# sensorNodev1_0.net
KiCad netlist of a schematic drawn in EAGLE
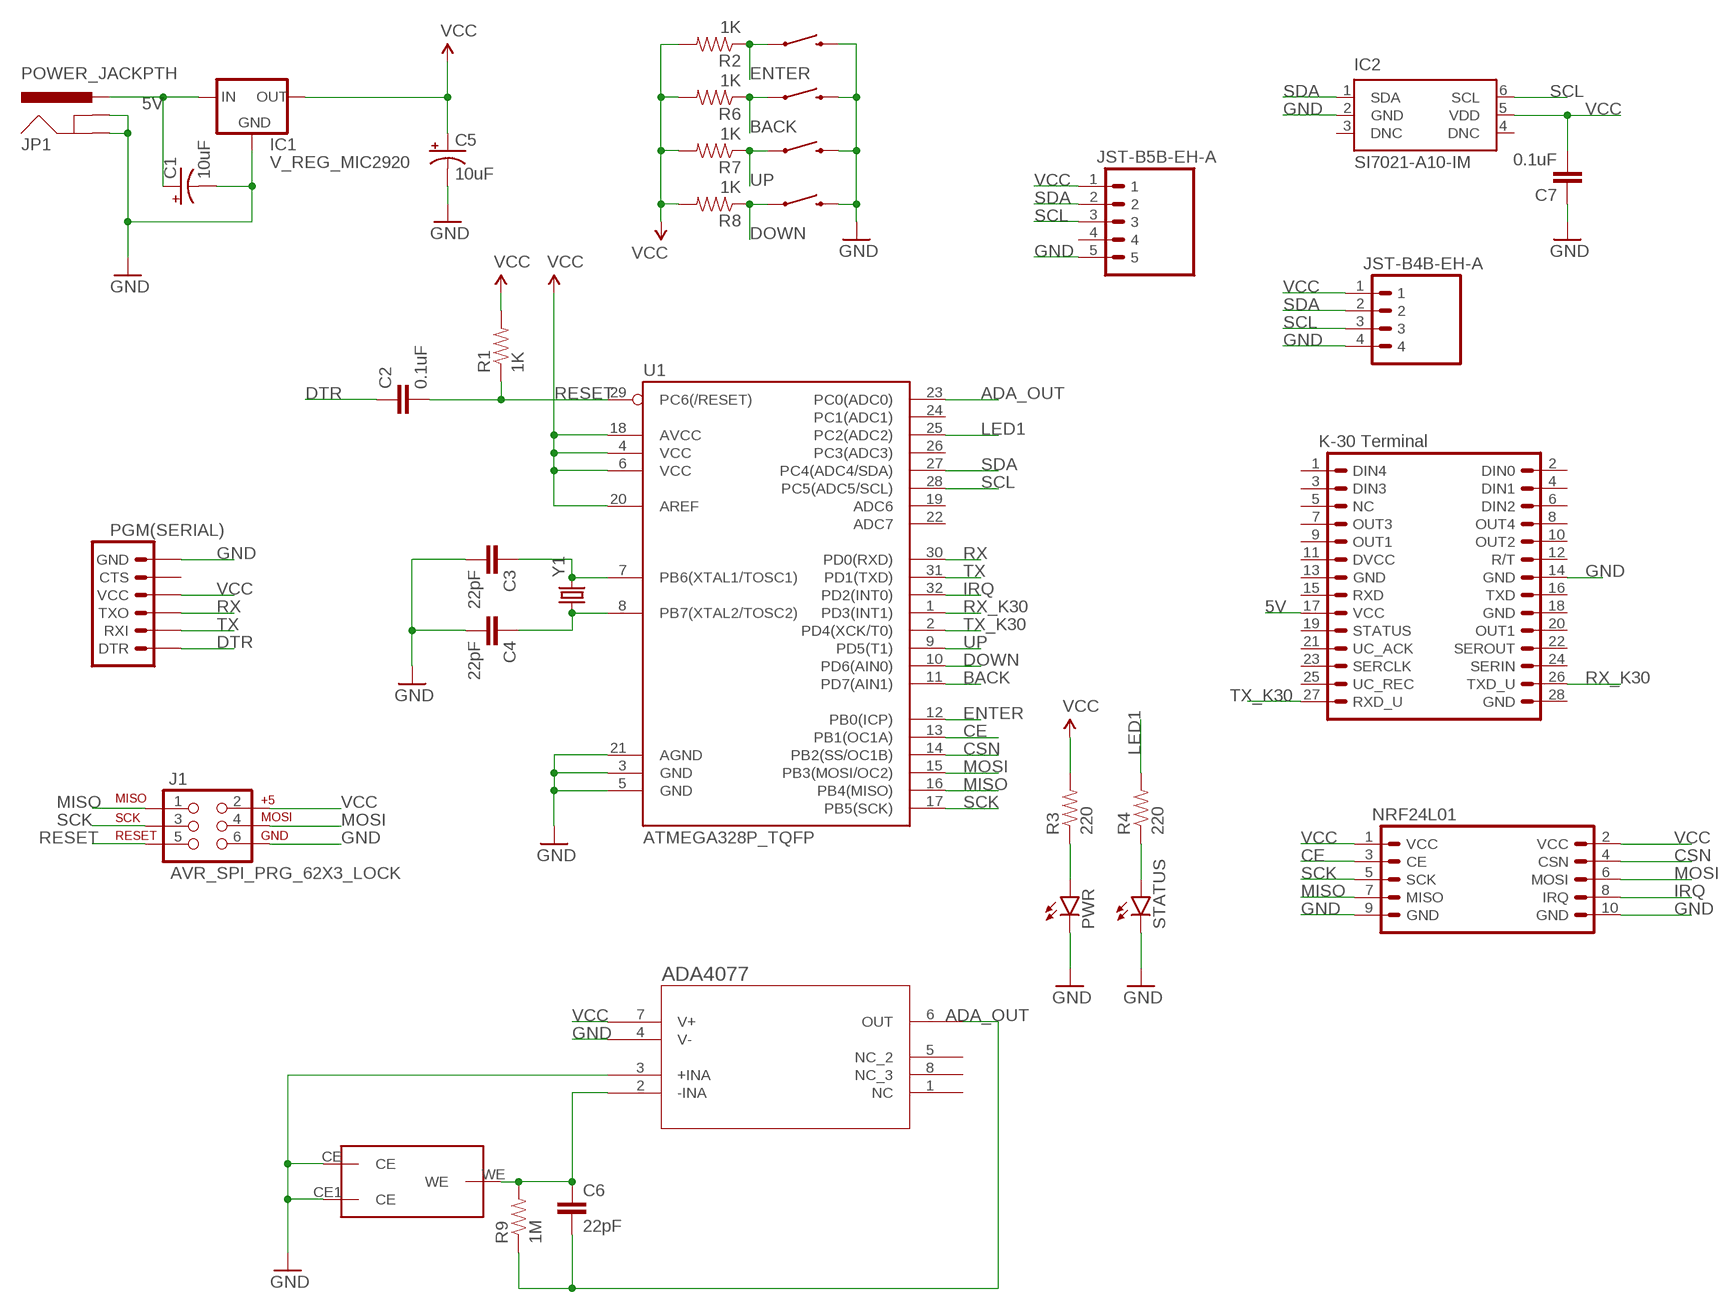
[diagram p0: schematic, sheet 1]

(export (version "E")
  (design (tool "Eeschema 10.0.6"))
  (components
    (comp (ref "BACK")
      (value "SWITCH-MOMENTARY-2SIDE_EZ")
      (footprint "eagle-import:TACTILE-PTH-SIDEEZ")
      (libsource (lib "eagle-import") (part "SWITCH-MOMENTARY-2SIDE_EZ"))
    )
    (comp (ref "C1")
      (value "10uF")
      (footprint "eagle-import:CPOL-RADIAL-10UF-25V")
      (libsource (lib "eagle-import") (part "CAP_POLPTH2"))
    )
    (comp (ref "C2")
      (value "0.1uF")
      (footprint "eagle-import:0603-CAP")
      (libsource (lib "eagle-import") (part "0.1UF-25V(+80/-20%)(0603)"))
    )
    (comp (ref "C3")
      (value "22pF")
      (footprint "eagle-import:0603-CAP")
      (libsource (lib "eagle-import") (part "22PF-50V-5%(0603)"))
    )
    (comp (ref "C4")
      (value "22pF")
      (footprint "eagle-import:0603-CAP")
      (libsource (lib "eagle-import") (part "22PF-50V-5%(0603)"))
    )
    (comp (ref "C5")
      (value "10uF")
      (footprint "eagle-import:CPOL-RADIAL-10UF-25V")
      (libsource (lib "eagle-import") (part "CAP_POLPTH2"))
    )
    (comp (ref "C6")
      (value "22pF")
      (footprint "eagle-import:0603-CAP")
      (libsource (lib "eagle-import") (part "22PF-50V-5%(0603)"))
    )
    (comp (ref "C7")
      (value "0.1uF")
      (footprint "eagle-import:0603-CAP")
      (libsource (lib "eagle-import") (part "0.1UF-25V(+80/-20%)(0603)"))
    )
    (comp (ref "CO2")
      (value "K-30K-30")
      (footprint "eagle-import:K-30")
      (libsource (lib "eagle-import") (part "K-30K-30"))
    )
    (comp (ref "DOWN")
      (value "SWITCH-MOMENTARY-2SIDE_EZ")
      (footprint "eagle-import:TACTILE-PTH-SIDEEZ")
      (libsource (lib "eagle-import") (part "SWITCH-MOMENTARY-2SIDE_EZ"))
    )
    (comp (ref "ENTER")
      (value "SWITCH-MOMENTARY-2SIDE_EZ")
      (footprint "eagle-import:TACTILE-PTH-SIDEEZ")
      (libsource (lib "eagle-import") (part "SWITCH-MOMENTARY-2SIDE_EZ"))
    )
    (comp (ref "IC1")
      (value "V_REG_MIC2920")
      (footprint "eagle-import:SOT223")
      (libsource (lib "eagle-import") (part "V_REG_MIC2920"))
    )
    (comp (ref "IC2")
      (value "SI7021-A10-IM")
      (footprint "eagle-import:DFN6-3X3")
      (fields (field (name "MF") "Silicon Labs") (field (name "MPN") "Si7021-A10-IM"))
      (libsource (lib "eagle-import") (part "SI7021-A10-IM"))
    )
    (comp (ref "J1")
      (value "AVR_SPI_PRG_62X3_LOCK")
      (footprint "eagle-import:2X3_LOCK")
      (libsource (lib "eagle-import") (part "AVR_SPI_PRG_62X3_LOCK"))
    )
    (comp (ref "JP1")
      (value "POWER_JACKPTH")
      (footprint "eagle-import:POWER_JACK_PTH")
      (libsource (lib "eagle-import") (part "POWER_JACKPTH"))
    )
    (comp (ref "LIGHT")
      (value "JST-B4B-EH-A")
      (footprint "eagle-import:JST-B4B-ED-A")
      (libsource (lib "eagle-import") (part "JST-B4B-EH-A"))
    )
    (comp (ref "PGM(SERIAL)")
      (value "ARDUINO_SERIAL_PROGRAMPTH")
      (footprint "eagle-import:1X06")
      (libsource (lib "eagle-import") (part "ARDUINO_SERIAL_PROGRAMPTH"))
    )
    (comp (ref "PWR")
      (value "LED0603")
      (footprint "eagle-import:LED-0603")
      (libsource (lib "eagle-import") (part "LED0603"))
    )
    (comp (ref "R1")
      (value "1K")
      (footprint "eagle-import:0603-RES")
      (libsource (lib "eagle-import") (part "1KOHM-1/10W-1%(0603)"))
    )
    (comp (ref "R2")
      (value "1K")
      (footprint "eagle-import:0603-RES")
      (libsource (lib "eagle-import") (part "1KOHM-1/10W-1%(0603)"))
    )
    (comp (ref "R3")
      (value "220")
      (footprint "eagle-import:0603-RES")
      (libsource (lib "eagle-import") (part "1KOHM-1/10W-1%(0603)"))
    )
    (comp (ref "R4")
      (value "220")
      (footprint "eagle-import:0603-RES")
      (libsource (lib "eagle-import") (part "1KOHM-1/10W-1%(0603)"))
    )
    (comp (ref "R6")
      (value "1K")
      (footprint "eagle-import:0603-RES")
      (libsource (lib "eagle-import") (part "1KOHM-1/10W-1%(0603)"))
    )
    (comp (ref "R7")
      (value "1K")
      (footprint "eagle-import:0603-RES")
      (libsource (lib "eagle-import") (part "1KOHM-1/10W-1%(0603)"))
    )
    (comp (ref "R8")
      (value "1K")
      (footprint "eagle-import:0603-RES")
      (libsource (lib "eagle-import") (part "1KOHM-1/10W-1%(0603)"))
    )
    (comp (ref "R9")
      (value "1M")
      (footprint "eagle-import:0603-RES")
      (libsource (lib "eagle-import") (part "1KOHM-1/10W-1%(0603)"))
    )
    (comp (ref "SCREEN")
      (value "JST-B5B-EH-A")
      (footprint "eagle-import:JST-B5B-ED-A")
      (libsource (lib "eagle-import") (part "JST-B5B-EH-A"))
    )
    (comp (ref "STATUS")
      (value "LED0603")
      (footprint "eagle-import:LED-0603")
      (libsource (lib "eagle-import") (part "LED0603"))
    )
    (comp (ref "U$1")
      (value "TGS5042A")
      (footprint "eagle-import:TGS5042")
      (libsource (lib "eagle-import") (part "TGS5042A"))
    )
    (comp (ref "U$2")
      (value "NRF24L01")
      (footprint "eagle-import:NRF24L01")
      (libsource (lib "eagle-import") (part "NRF24L01"))
    )
    (comp (ref "U1")
      (value "ATMEGA328P_TQFP")
      (footprint "eagle-import:TQFP32-08")
      (libsource (lib "eagle-import") (part "ATMEGA328P_TQFP"))
    )
    (comp (ref "U2")
      (value "ADA4077-1ARZ")
      (footprint "eagle-import:R_8")
      (libsource (lib "eagle-import") (part "ADA4077-1ARZ"))
    )
    (comp (ref "UP")
      (value "SWITCH-MOMENTARY-2SIDE_EZ")
      (footprint "eagle-import:TACTILE-PTH-SIDEEZ")
      (libsource (lib "eagle-import") (part "SWITCH-MOMENTARY-2SIDE_EZ"))
    )
    (comp (ref "Y1")
      (value "CRYSTALHC49US")
      (footprint "eagle-import:HC49US")
      (libsource (lib "eagle-import") (part "CRYSTALHC49US"))
    )
  )
  (nets
    (net (code "1") (name "/5V") (class "Default")
      (node (ref "C1") (pin "1") (pinfunction "+_1") (pintype "passive"))
      (node (ref "CO2") (pin "17") (pinfunction "VCC_17") (pintype "bidirectional"))
      (node (ref "IC1") (pin "1") (pinfunction "IN_1") (pintype "input"))
      (node (ref "JP1") (pin "PWR") (pinfunction "PWR_PWR") (pintype "bidirectional"))
    )
    (net (code "2") (name "/ADA_OUT") (class "Default")
      (node (ref "C6") (pin "2") (pinfunction "2_2") (pintype "passive"))
      (node (ref "R9") (pin "1") (pinfunction "1_1") (pintype "passive"))
      (node (ref "U1") (pin "23") (pinfunction "PC0(ADC0)_23") (pintype "bidirectional"))
      (node (ref "U2") (pin "6") (pinfunction "OUT_6") (pintype "passive"))
    )
    (net (code "3") (name "/BACK") (class "Default")
      (node (ref "BACK") (pin "1") (pinfunction "1_1") (pintype "passive"))
      (node (ref "R6") (pin "1") (pinfunction "1_1") (pintype "passive"))
      (node (ref "U1") (pin "11") (pinfunction "PD7(AIN1)_11") (pintype "bidirectional"))
    )
    (net (code "4") (name "/CE") (class "Default")
      (node (ref "U$2") (pin "3") (pinfunction "CE_3") (pintype "bidirectional"))
      (node (ref "U1") (pin "13") (pinfunction "PB1(OC1A)_13") (pintype "bidirectional"))
    )
    (net (code "5") (name "/CSN") (class "Default")
      (node (ref "U$2") (pin "4") (pinfunction "CSN_4") (pintype "bidirectional"))
      (node (ref "U1") (pin "14") (pinfunction "PB2(SS/OC1B)_14") (pintype "bidirectional"))
    )
    (net (code "6") (name "/DOWN") (class "Default")
      (node (ref "DOWN") (pin "1") (pinfunction "1_1") (pintype "passive"))
      (node (ref "R8") (pin "1") (pinfunction "1_1") (pintype "passive"))
      (node (ref "U1") (pin "10") (pinfunction "PD6(AIN0)_10") (pintype "bidirectional"))
    )
    (net (code "7") (name "/DTR") (class "Default")
      (node (ref "C2") (pin "1") (pinfunction "1_1") (pintype "passive"))
      (node (ref "PGM(SERIAL)") (pin "1") (pinfunction "DTR_1") (pintype "passive"))
    )
    (net (code "8") (name "/ENTER") (class "Default")
      (node (ref "ENTER") (pin "1") (pinfunction "1_1") (pintype "passive"))
      (node (ref "R2") (pin "1") (pinfunction "1_1") (pintype "passive"))
      (node (ref "U1") (pin "12") (pinfunction "PB0(ICP)_12") (pintype "bidirectional"))
    )
    (net (code "9") (name "/IRQ") (class "Default")
      (node (ref "U$2") (pin "8") (pinfunction "IRQ_8") (pintype "bidirectional"))
      (node (ref "U1") (pin "32") (pinfunction "PD2(INT0)_32") (pintype "bidirectional"))
    )
    (net (code "10") (name "/LED1") (class "Default")
      (node (ref "R4") (pin "2") (pinfunction "2_2") (pintype "passive"))
      (node (ref "U1") (pin "25") (pinfunction "PC2(ADC2)_25") (pintype "bidirectional"))
    )
    (net (code "11") (name "/MISO") (class "Default")
      (node (ref "J1") (pin "1") (pinfunction "1_1") (pintype "passive"))
      (node (ref "U$2") (pin "7") (pinfunction "MISO_7") (pintype "bidirectional"))
      (node (ref "U1") (pin "16") (pinfunction "PB4(MISO)_16") (pintype "bidirectional"))
    )
    (net (code "12") (name "/MOSI") (class "Default")
      (node (ref "J1") (pin "4") (pinfunction "4_4") (pintype "passive"))
      (node (ref "U$2") (pin "6") (pinfunction "MOSI_6") (pintype "bidirectional"))
      (node (ref "U1") (pin "15") (pinfunction "PB3(MOSI/OC2)_15") (pintype "bidirectional"))
    )
    (net (code "13") (name "/RESET") (class "Default")
      (node (ref "C2") (pin "2") (pinfunction "2_2") (pintype "passive"))
      (node (ref "J1") (pin "5") (pinfunction "5_5") (pintype "passive"))
      (node (ref "R1") (pin "1") (pinfunction "1_1") (pintype "passive"))
      (node (ref "U1") (pin "29") (pinfunction "PC6(/RESET)_29") (pintype "bidirectional"))
    )
    (net (code "14") (name "/RX") (class "Default")
      (node (ref "PGM(SERIAL)") (pin "3") (pinfunction "TXO_3") (pintype "passive"))
      (node (ref "U1") (pin "30") (pinfunction "PD0(RXD)_30") (pintype "bidirectional"))
    )
    (net (code "15") (name "/RX_K30") (class "Default")
      (node (ref "CO2") (pin "26") (pinfunction "TXD_U_26") (pintype "bidirectional"))
      (node (ref "U1") (pin "1") (pinfunction "PD3(INT1)_1") (pintype "bidirectional"))
    )
    (net (code "16") (name "/SCK") (class "Default")
      (node (ref "J1") (pin "3") (pinfunction "3_3") (pintype "passive"))
      (node (ref "U$2") (pin "5") (pinfunction "SCK_5") (pintype "bidirectional"))
      (node (ref "U1") (pin "17") (pinfunction "PB5(SCK)_17") (pintype "bidirectional"))
    )
    (net (code "17") (name "/SCL") (class "Default")
      (node (ref "IC2") (pin "6") (pinfunction "SCL_6") (pintype "input"))
      (node (ref "LIGHT") (pin "3") (pinfunction "3_3") (pintype "bidirectional"))
      (node (ref "SCREEN") (pin "3") (pinfunction "3_3") (pintype "bidirectional"))
      (node (ref "U1") (pin "28") (pinfunction "PC5(ADC5/SCL)_28") (pintype "bidirectional"))
    )
    (net (code "18") (name "/SDA") (class "Default")
      (node (ref "IC2") (pin "1") (pinfunction "SDA_1") (pintype "bidirectional"))
      (node (ref "LIGHT") (pin "2") (pinfunction "2_2") (pintype "bidirectional"))
      (node (ref "SCREEN") (pin "2") (pinfunction "2_2") (pintype "bidirectional"))
      (node (ref "U1") (pin "27") (pinfunction "PC4(ADC4/SDA)_27") (pintype "bidirectional"))
    )
    (net (code "19") (name "/TX") (class "Default")
      (node (ref "PGM(SERIAL)") (pin "2") (pinfunction "RXI_2") (pintype "passive"))
      (node (ref "U1") (pin "31") (pinfunction "PD1(TXD)_31") (pintype "bidirectional"))
    )
    (net (code "20") (name "/TX_K30") (class "Default")
      (node (ref "CO2") (pin "27") (pinfunction "RXD_U_27") (pintype "bidirectional"))
      (node (ref "U1") (pin "2") (pinfunction "PD4(XCK/T0)_2") (pintype "bidirectional"))
    )
    (net (code "21") (name "/UP") (class "Default")
      (node (ref "R7") (pin "1") (pinfunction "1_1") (pintype "passive"))
      (node (ref "U1") (pin "9") (pinfunction "PD5(T1)_9") (pintype "bidirectional"))
      (node (ref "UP") (pin "1") (pinfunction "1_1") (pintype "passive"))
    )
    (net (code "22") (name "GND") (class "Default")
      (node (ref "BACK") (pin "2") (pinfunction "2_2") (pintype "passive"))
      (node (ref "C1") (pin "2") (pinfunction "-_2") (pintype "passive"))
      (node (ref "C3") (pin "2") (pinfunction "2_2") (pintype "passive"))
      (node (ref "C4") (pin "2") (pinfunction "2_2") (pintype "passive"))
      (node (ref "C5") (pin "2") (pinfunction "-_2") (pintype "passive"))
      (node (ref "C7") (pin "1") (pinfunction "1_1") (pintype "passive"))
      (node (ref "CO2") (pin "14") (pinfunction "GND_14") (pintype "bidirectional"))
      (node (ref "DOWN") (pin "2") (pinfunction "2_2") (pintype "passive"))
      (node (ref "ENTER") (pin "2") (pinfunction "2_2") (pintype "passive"))
      (node (ref "IC1") (pin "2") (pinfunction "GND_2") (pintype "input"))
      (node (ref "IC2") (pin "2") (pinfunction "GND_2") (pintype "power_in"))
      (node (ref "J1") (pin "6") (pinfunction "6_6") (pintype "passive"))
      (node (ref "JP1") (pin "GND") (pinfunction "GND_GND") (pintype "bidirectional"))
      (node (ref "JP1") (pin "GNDBREAK") (pinfunction "GNDBREAK_GNDBREAK") (pintype "bidirectional"))
      (node (ref "LIGHT") (pin "4") (pinfunction "4_4") (pintype "bidirectional"))
      (node (ref "PGM(SERIAL)") (pin "6") (pinfunction "GND_6") (pintype "passive"))
      (node (ref "PWR") (pin "C") (pinfunction "C_C") (pintype "passive"))
      (node (ref "SCREEN") (pin "5") (pinfunction "5_5") (pintype "bidirectional"))
      (node (ref "STATUS") (pin "C") (pinfunction "C_C") (pintype "passive"))
      (node (ref "U$1") (pin "CE") (pinfunction "CE_CE") (pintype "bidirectional"))
      (node (ref "U$1") (pin "CE1") (pinfunction "CE_CE1") (pintype "bidirectional"))
      (node (ref "U$2") (pin "10") (pinfunction "GND_10") (pintype "bidirectional"))
      (node (ref "U$2") (pin "9") (pinfunction "GND_9") (pintype "bidirectional"))
      (node (ref "U1") (pin "21") (pinfunction "AGND_21") (pintype "bidirectional"))
      (node (ref "U1") (pin "3") (pinfunction "GND_3") (pintype "bidirectional"))
      (node (ref "U1") (pin "5") (pinfunction "GND_5") (pintype "bidirectional"))
      (node (ref "U2") (pin "3") (pinfunction "+INA_3") (pintype "passive"))
      (node (ref "U2") (pin "4") (pinfunction "V-_4") (pintype "passive"))
      (node (ref "UP") (pin "2") (pinfunction "2_2") (pintype "passive"))
    )
    (net (code "23") (name "Net-(PWR-PadA)") (class "Default")
      (node (ref "PWR") (pin "A") (pinfunction "A_A") (pintype "passive"))
      (node (ref "R3") (pin "1") (pinfunction "1_1") (pintype "passive"))
    )
    (net (code "24") (name "Net-(R4-Pad1)") (class "Default")
      (node (ref "R4") (pin "1") (pinfunction "1_1") (pintype "passive"))
      (node (ref "STATUS") (pin "A") (pinfunction "A_A") (pintype "passive"))
    )
    (net (code "25") (name "Net-(U1-PB6(XTAL1{slash}TOSC1))") (class "Default")
      (node (ref "C3") (pin "1") (pinfunction "1_1") (pintype "passive"))
      (node (ref "U1") (pin "7") (pinfunction "PB6(XTAL1/TOSC1)_7") (pintype "bidirectional"))
      (node (ref "Y1") (pin "2") (pinfunction "2_2") (pintype "passive"))
    )
    (net (code "26") (name "Net-(U1-PB7(XTAL2{slash}TOSC2))") (class "Default")
      (node (ref "C4") (pin "1") (pinfunction "1_1") (pintype "passive"))
      (node (ref "U1") (pin "8") (pinfunction "PB7(XTAL2/TOSC2)_8") (pintype "bidirectional"))
      (node (ref "Y1") (pin "1") (pinfunction "1_1") (pintype "passive"))
    )
    (net (code "27") (name "Net-(U2--INA)") (class "Default")
      (node (ref "C6") (pin "1") (pinfunction "1_1") (pintype "passive"))
      (node (ref "R9") (pin "2") (pinfunction "2_2") (pintype "passive"))
      (node (ref "U$1") (pin "WE") (pinfunction "WE_WE") (pintype "bidirectional"))
      (node (ref "U2") (pin "2") (pinfunction "-INA_2") (pintype "passive"))
    )
    (net (code "28") (name "VCC") (class "Default")
      (node (ref "C5") (pin "1") (pinfunction "+_1") (pintype "passive"))
      (node (ref "C7") (pin "2") (pinfunction "2_2") (pintype "passive"))
      (node (ref "IC1") (pin "3") (pinfunction "OUT_3") (pintype "output"))
      (node (ref "IC2") (pin "5") (pinfunction "VDD_5") (pintype "power_in"))
      (node (ref "J1") (pin "2") (pinfunction "2_2") (pintype "passive"))
      (node (ref "LIGHT") (pin "1") (pinfunction "1_1") (pintype "bidirectional"))
      (node (ref "PGM(SERIAL)") (pin "4") (pinfunction "VCC_4") (pintype "passive"))
      (node (ref "R1") (pin "2") (pinfunction "2_2") (pintype "passive"))
      (node (ref "R2") (pin "2") (pinfunction "2_2") (pintype "passive"))
      (node (ref "R3") (pin "2") (pinfunction "2_2") (pintype "passive"))
      (node (ref "R6") (pin "2") (pinfunction "2_2") (pintype "passive"))
      (node (ref "R7") (pin "2") (pinfunction "2_2") (pintype "passive"))
      (node (ref "R8") (pin "2") (pinfunction "2_2") (pintype "passive"))
      (node (ref "SCREEN") (pin "1") (pinfunction "1_1") (pintype "bidirectional"))
      (node (ref "U$2") (pin "1") (pinfunction "VCC_1") (pintype "bidirectional"))
      (node (ref "U$2") (pin "2") (pinfunction "VCC_2") (pintype "bidirectional"))
      (node (ref "U1") (pin "18") (pinfunction "AVCC_18") (pintype "bidirectional"))
      (node (ref "U1") (pin "20") (pinfunction "AREF_20") (pintype "bidirectional"))
      (node (ref "U1") (pin "4") (pinfunction "VCC_4") (pintype "bidirectional"))
      (node (ref "U1") (pin "6") (pinfunction "VCC_6") (pintype "bidirectional"))
      (node (ref "U2") (pin "7") (pinfunction "V+_7") (pintype "passive"))
    )
    (net (code "29") (name "unconnected-(CO2-DIN0-Pad2)") (class "Default")
      (node (ref "CO2") (pin "2") (pinfunction "DIN0_2") (pintype "bidirectional"))
    )
    (net (code "30") (name "unconnected-(CO2-DIN1-Pad4)") (class "Default")
      (node (ref "CO2") (pin "4") (pinfunction "DIN1_4") (pintype "bidirectional"))
    )
    (net (code "31") (name "unconnected-(CO2-DIN2-Pad6)") (class "Default")
      (node (ref "CO2") (pin "6") (pinfunction "DIN2_6") (pintype "bidirectional"))
    )
    (net (code "32") (name "unconnected-(CO2-DIN3-Pad3)") (class "Default")
      (node (ref "CO2") (pin "3") (pinfunction "DIN3_3") (pintype "bidirectional"))
    )
    (net (code "33") (name "unconnected-(CO2-DIN4-Pad1)") (class "Default")
      (node (ref "CO2") (pin "1") (pinfunction "DIN4_1") (pintype "bidirectional"))
    )
    (net (code "34") (name "unconnected-(CO2-DVCC-Pad11)") (class "Default")
      (node (ref "CO2") (pin "11") (pinfunction "DVCC_11") (pintype "bidirectional"))
    )
    (net (code "35") (name "unconnected-(CO2-GND-Pad13)") (class "Default")
      (node (ref "CO2") (pin "13") (pinfunction "GND_13") (pintype "bidirectional"))
    )
    (net (code "36") (name "unconnected-(CO2-GND-Pad18)") (class "Default")
      (node (ref "CO2") (pin "18") (pinfunction "GND_18") (pintype "bidirectional"))
    )
    (net (code "37") (name "unconnected-(CO2-GND-Pad28)") (class "Default")
      (node (ref "CO2") (pin "28") (pinfunction "GND_28") (pintype "bidirectional"))
    )
    (net (code "38") (name "unconnected-(CO2-NC-Pad5)") (class "Default")
      (node (ref "CO2") (pin "5") (pinfunction "NC_5") (pintype "bidirectional"))
    )
    (net (code "39") (name "unconnected-(CO2-OUT1-Pad9)") (class "Default")
      (node (ref "CO2") (pin "9") (pinfunction "OUT1_9") (pintype "bidirectional"))
    )
    (net (code "40") (name "unconnected-(CO2-OUT1-Pad20)") (class "Default")
      (node (ref "CO2") (pin "20") (pinfunction "OUT1_20") (pintype "bidirectional"))
    )
    (net (code "41") (name "unconnected-(CO2-OUT2-Pad10)") (class "Default")
      (node (ref "CO2") (pin "10") (pinfunction "OUT2_10") (pintype "bidirectional"))
    )
    (net (code "42") (name "unconnected-(CO2-OUT3-Pad7)") (class "Default")
      (node (ref "CO2") (pin "7") (pinfunction "OUT3_7") (pintype "bidirectional"))
    )
    (net (code "43") (name "unconnected-(CO2-OUT4-Pad8)") (class "Default")
      (node (ref "CO2") (pin "8") (pinfunction "OUT4_8") (pintype "bidirectional"))
    )
    (net (code "44") (name "unconnected-(CO2-RXD-Pad15)") (class "Default")
      (node (ref "CO2") (pin "15") (pinfunction "RXD_15") (pintype "bidirectional"))
    )
    (net (code "45") (name "unconnected-(CO2-R{slash}T-Pad12)") (class "Default")
      (node (ref "CO2") (pin "12") (pinfunction "R/T_12") (pintype "bidirectional"))
    )
    (net (code "46") (name "unconnected-(CO2-SERCLK-Pad23)") (class "Default")
      (node (ref "CO2") (pin "23") (pinfunction "SERCLK_23") (pintype "bidirectional"))
    )
    (net (code "47") (name "unconnected-(CO2-SERIN-Pad24)") (class "Default")
      (node (ref "CO2") (pin "24") (pinfunction "SERIN_24") (pintype "bidirectional"))
    )
    (net (code "48") (name "unconnected-(CO2-SEROUT-Pad22)") (class "Default")
      (node (ref "CO2") (pin "22") (pinfunction "SEROUT_22") (pintype "bidirectional"))
    )
    (net (code "49") (name "unconnected-(CO2-STATUS-Pad19)") (class "Default")
      (node (ref "CO2") (pin "19") (pinfunction "STATUS_19") (pintype "bidirectional"))
    )
    (net (code "50") (name "unconnected-(CO2-TXD-Pad16)") (class "Default")
      (node (ref "CO2") (pin "16") (pinfunction "TXD_16") (pintype "bidirectional"))
    )
    (net (code "51") (name "unconnected-(CO2-UC_ACK-Pad21)") (class "Default")
      (node (ref "CO2") (pin "21") (pinfunction "UC_ACK_21") (pintype "bidirectional"))
    )
    (net (code "52") (name "unconnected-(CO2-UC_REC-Pad25)") (class "Default")
      (node (ref "CO2") (pin "25") (pinfunction "UC_REC_25") (pintype "bidirectional"))
    )
    (net (code "53") (name "unconnected-(IC2-DNC-Pad3)") (class "Default")
      (node (ref "IC2") (pin "3") (pinfunction "DNC_3") (pintype "no_connect"))
    )
    (net (code "54") (name "unconnected-(IC2-DNC-Pad4)") (class "Default")
      (node (ref "IC2") (pin "4") (pinfunction "DNC_4") (pintype "no_connect"))
    )
    (net (code "55") (name "unconnected-(PGM(SERIAL)-CTS-Pad5)") (class "Default")
      (node (ref "PGM(SERIAL)") (pin "5") (pinfunction "CTS_5") (pintype "passive"))
    )
    (net (code "56") (name "unconnected-(SCREEN-Pad4)") (class "Default")
      (node (ref "SCREEN") (pin "4") (pinfunction "4_4") (pintype "bidirectional"))
    )
    (net (code "57") (name "unconnected-(U1-ADC6-Pad19)") (class "Default")
      (node (ref "U1") (pin "19") (pinfunction "ADC6_19") (pintype "bidirectional"))
    )
    (net (code "58") (name "unconnected-(U1-ADC7-Pad22)") (class "Default")
      (node (ref "U1") (pin "22") (pinfunction "ADC7_22") (pintype "bidirectional"))
    )
    (net (code "59") (name "unconnected-(U1-PC1(ADC1)-Pad24)") (class "Default")
      (node (ref "U1") (pin "24") (pinfunction "PC1(ADC1)_24") (pintype "bidirectional"))
    )
    (net (code "60") (name "unconnected-(U1-PC3(ADC3)-Pad26)") (class "Default")
      (node (ref "U1") (pin "26") (pinfunction "PC3(ADC3)_26") (pintype "bidirectional"))
    )
    (net (code "61") (name "unconnected-(U2-NC-Pad1)") (class "Default")
      (node (ref "U2") (pin "1") (pinfunction "NC_1") (pintype "passive"))
    )
    (net (code "62") (name "unconnected-(U2-NC_2-Pad5)") (class "Default")
      (node (ref "U2") (pin "5") (pinfunction "NC_2_5") (pintype "passive"))
    )
    (net (code "63") (name "unconnected-(U2-NC_3-Pad8)") (class "Default")
      (node (ref "U2") (pin "8") (pinfunction "NC_3_8") (pintype "passive"))
    )
  )
)
